# 5137_Pins_Schematic.net
KiCad netlist of a schematic drawn in EAGLE
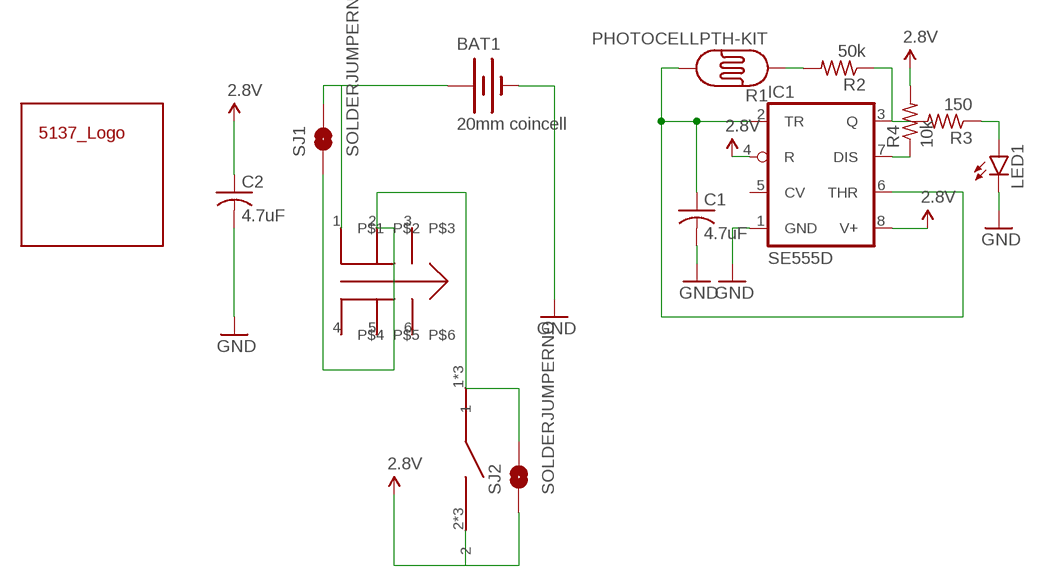
[diagram p0: schematic, sheet 1]

(export (version "E")
  (design (tool "Eeschema 10.0.6"))
  (components
    (comp (ref "BAT1")
      (value "20mm coincell")
      (footprint "eagle-import:BATTCON_20MM_4LEGS")
      (libsource (lib "eagle-import") (part "BATTERY20MM_4LEGS"))
    )
    (comp (ref "C1")
      (value "4.7uF")
      (footprint "eagle-import:C1206K")
      (libsource (lib "eagle-import") (part "C-USC1206K"))
    )
    (comp (ref "C2")
      (value "4.7uF")
      (footprint "eagle-import:C1206K")
      (libsource (lib "eagle-import") (part "C-USC1206K"))
    )
    (comp (ref "IC1")
      (value "SE555D")
      (footprint "eagle-import:SO08")
      (libsource (lib "eagle-import") (part "555DSE"))
    )
    (comp (ref "LED1")
      (value "LED5MM-KIT")
      (footprint "eagle-import:LED5MM-KIT")
      (libsource (lib "eagle-import") (part "LED5MM-KIT"))
    )
    (comp (ref "R1")
      (value "PHOTOCELLPTH-KIT")
      (footprint "eagle-import:PHOTOCELL-KIT")
      (libsource (lib "eagle-import") (part "PHOTOCELLPTH-KIT"))
    )
    (comp (ref "R2")
      (value "50k")
      (footprint "eagle-import:R1206W")
      (libsource (lib "eagle-import") (part "R-US_R1206W"))
    )
    (comp (ref "R3")
      (value "150")
      (footprint "eagle-import:R1206W")
      (libsource (lib "eagle-import") (part "R-US_R1206W"))
    )
    (comp (ref "R4")
      (value "10k")
      (footprint "eagle-import:R1206W")
      (libsource (lib "eagle-import") (part "R-US_R1206W"))
    )
    (comp (ref "SJ1")
      (value "SOLDERJUMPERNO")
      (footprint "eagle-import:SJ_2S-NO")
      (libsource (lib "eagle-import") (part "SOLDERJUMPERNO"))
    )
    (comp (ref "SJ2")
      (value "SOLDERJUMPERNO")
      (footprint "eagle-import:SJ_2S-NO")
      (libsource (lib "eagle-import") (part "SOLDERJUMPERNO"))
    )
    (comp (ref "U$1")
      (value "5137_LOGO_DEV")
      (footprint "eagle-import:5137_LOGO_PKG")
      (libsource (lib "eagle-import") (part "5137_LOGO_DEV"))
    )
    (comp (ref "U$2")
      (value "SAFETY_PIN_SWITCH")
      (footprint "eagle-import:SAFETY_PIN_SWITCH")
      (libsource (lib "eagle-import") (part "SAFETY_PIN_SWITCH"))
    )
    (comp (ref "U$3")
      (value "DPDT_GULL_WING_SWITCH")
      (footprint "eagle-import:DPDT_GULL_WING_SWITCH")
      (libsource (lib "eagle-import") (part "DPDT_GULL_WING_SWITCH"))
    )
  )
  (nets
    (net (code "1") (name "2.8V") (class "Default")
      (node (ref "C2") (pin "1") (pinfunction "1_1") (pintype "passive"))
      (node (ref "IC1") (pin "4") (pinfunction "R_4") (pintype "input"))
      (node (ref "IC1") (pin "8") (pinfunction "V+_8") (pintype "power_in"))
      (node (ref "R4") (pin "2") (pinfunction "2_2") (pintype "passive"))
      (node (ref "SJ2") (pin "1") (pinfunction "1_1") (pintype "passive"))
      (node (ref "U$2") (pin "2") (pinfunction "2_2") (pintype "bidirectional"))
      (node (ref "U$2") (pin "2A") (pinfunction "2_2A") (pintype "bidirectional"))
      (node (ref "U$2") (pin "2B") (pinfunction "2_2B") (pintype "bidirectional"))
    )
    (net (code "2") (name "GND") (class "Default")
      (node (ref "BAT1") (pin "2") (pinfunction "-_2") (pintype "power_in"))
      (node (ref "C1") (pin "2") (pinfunction "2_2") (pintype "passive"))
      (node (ref "C2") (pin "2") (pinfunction "2_2") (pintype "passive"))
      (node (ref "IC1") (pin "1") (pinfunction "GND_1") (pintype "power_in"))
      (node (ref "LED1") (pin "K") (pinfunction "C_K") (pintype "passive"))
    )
    (net (code "3") (name "Net-(BAT1-+)") (class "Default")
      (node (ref "BAT1") (pin "1") (pinfunction "+_1") (pintype "power_in"))
      (node (ref "SJ1") (pin "2") (pinfunction "2_2") (pintype "passive"))
      (node (ref "U$3") (pin "1") (pinfunction "P$1_1") (pintype "bidirectional"))
    )
    (net (code "4") (name "Net-(IC1-DIS)") (class "Default")
      (node (ref "IC1") (pin "7") (pinfunction "DIS_7") (pintype "input"))
      (node (ref "R4") (pin "1") (pinfunction "1_1") (pintype "passive"))
    )
    (net (code "5") (name "Net-(IC1-Q)") (class "Default")
      (node (ref "IC1") (pin "3") (pinfunction "Q_3") (pintype "output"))
      (node (ref "R2") (pin "1") (pinfunction "1_1") (pintype "passive"))
      (node (ref "R3") (pin "2") (pinfunction "2_2") (pintype "passive"))
    )
    (net (code "6") (name "Net-(IC1-THR)") (class "Default")
      (node (ref "C1") (pin "1") (pinfunction "1_1") (pintype "passive"))
      (node (ref "IC1") (pin "2") (pinfunction "TR_2") (pintype "input"))
      (node (ref "IC1") (pin "6") (pinfunction "THR_6") (pintype "input"))
      (node (ref "R1") (pin "2") (pinfunction "P$2_2") (pintype "bidirectional"))
    )
    (net (code "7") (name "Net-(LED1-PadA)") (class "Default")
      (node (ref "LED1") (pin "A") (pinfunction "A_A") (pintype "passive"))
      (node (ref "R3") (pin "1") (pinfunction "1_1") (pintype "passive"))
    )
    (net (code "8") (name "Net-(R1-P$1)") (class "Default")
      (node (ref "R1") (pin "1") (pinfunction "P$1_1") (pintype "bidirectional"))
      (node (ref "R2") (pin "2") (pinfunction "2_2") (pintype "passive"))
    )
    (net (code "9") (name "Net-(U$3-P$2)") (class "Default")
      (node (ref "SJ1") (pin "1") (pinfunction "1_1") (pintype "passive"))
      (node (ref "SJ2") (pin "2") (pinfunction "2_2") (pintype "passive"))
      (node (ref "U$2") (pin "1") (pinfunction "1_1") (pintype "bidirectional"))
      (node (ref "U$2") (pin "1A") (pinfunction "1_1A") (pintype "bidirectional"))
      (node (ref "U$2") (pin "1B") (pinfunction "1_1B") (pintype "bidirectional"))
      (node (ref "U$3") (pin "2") (pinfunction "P$2_2") (pintype "bidirectional"))
    )
    (net (code "10") (name "unconnected-(IC1-CV-Pad5)") (class "Default")
      (node (ref "IC1") (pin "5") (pinfunction "CV_5") (pintype "input"))
    )
    (net (code "11") (name "unconnected-(U$3-P$3-Pad3)") (class "Default")
      (node (ref "U$3") (pin "3") (pinfunction "P$3_3") (pintype "bidirectional"))
    )
    (net (code "12") (name "unconnected-(U$3-P$4-Pad4)") (class "Default")
      (node (ref "U$3") (pin "4") (pinfunction "P$4_4") (pintype "bidirectional"))
    )
    (net (code "13") (name "unconnected-(U$3-P$5-Pad5)") (class "Default")
      (node (ref "U$3") (pin "5") (pinfunction "P$5_5") (pintype "bidirectional"))
    )
    (net (code "14") (name "unconnected-(U$3-P$6-Pad6)") (class "Default")
      (node (ref "U$3") (pin "6") (pinfunction "P$6_6") (pintype "bidirectional"))
    )
  )
)
